# robocon_task1.net
KiCad netlist of a schematic drawn in EAGLE
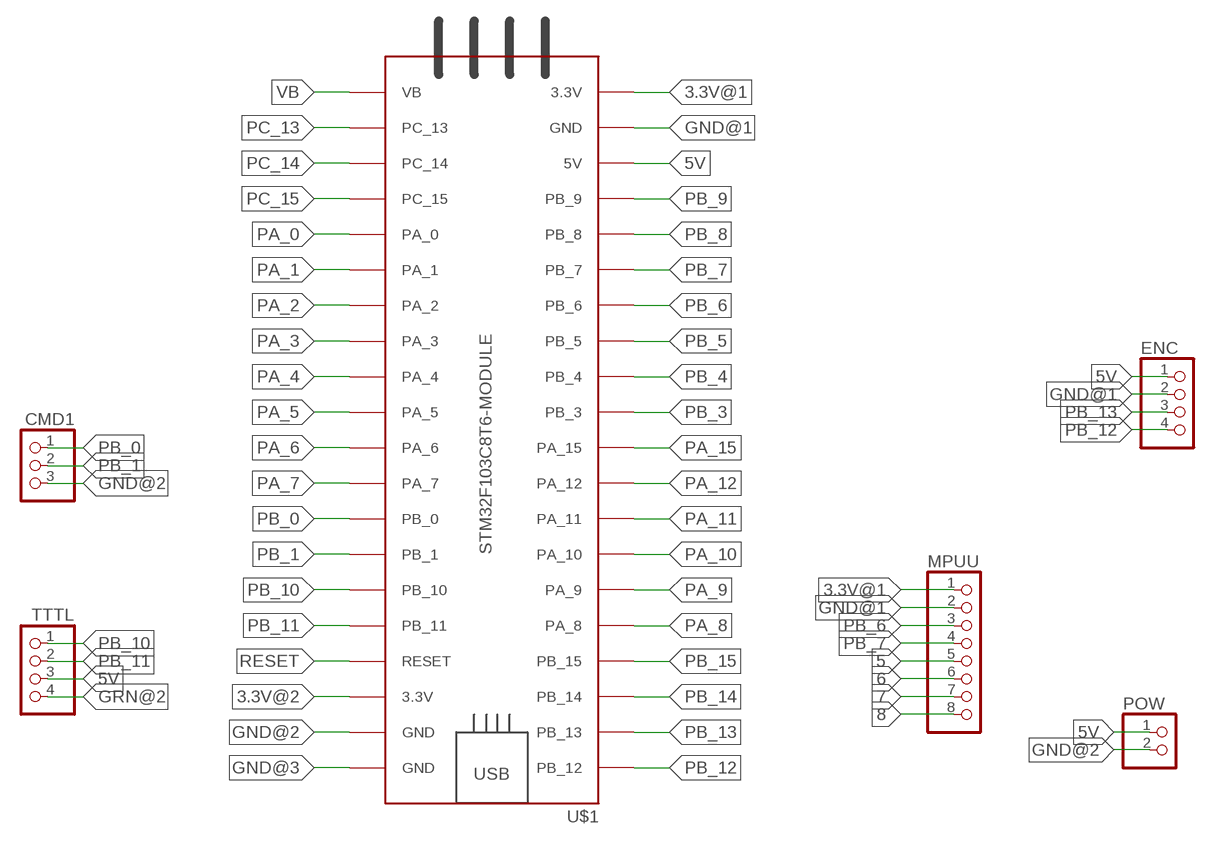
[diagram p0: schematic, sheet 1]

(export (version "E")
  (design (tool "Eeschema 10.0.6"))
  (components
    (comp (ref "CMD1")
      (value "PINHD-1X3")
      (footprint "eagle-import:1X03")
      (libsource (lib "eagle-import") (part "PINHD-1X3"))
    )
    (comp (ref "ENC")
      (value "PINHD-1X4")
      (footprint "eagle-import:1X04")
      (libsource (lib "eagle-import") (part "PINHD-1X4"))
    )
    (comp (ref "MPUU")
      (value "PINHD-1X8")
      (footprint "eagle-import:1X08")
      (libsource (lib "eagle-import") (part "PINHD-1X8"))
    )
    (comp (ref "POW")
      (value "PINHD-2_DATA")
      (footprint "eagle-import:1X02_DATA")
      (libsource (lib "eagle-import") (part "PINHD-2_DATA"))
    )
    (comp (ref "TTTL")
      (value "PINHD-4_DATA")
      (footprint "eagle-import:1X04_DATA")
      (libsource (lib "eagle-import") (part "PINHD-4_DATA"))
    )
    (comp (ref "U$1")
      (value "STM32F103C8T6-MODULE")
      (footprint "eagle-import:STM32F103C8T6-MODULE")
      (libsource (lib "eagle-import") (part "STM32F103C8T6-MODULE"))
    )
  )
  (nets
    (net (code "1") (name "3.3V@1") (class "Default")
      (node (ref "MPUU") (pin "1") (pinfunction "1_1") (pintype "passive"))
      (node (ref "U$1") (pin "3.3V_1") (pinfunction "3.3V_3.3V_1") (pintype "bidirectional"))
    )
    (net (code "2") (name "3.3V@2") (class "Default")
      (node (ref "U$1") (pin "3.3V_2") (pinfunction "3.3V_3.3V_2") (pintype "bidirectional"))
    )
    (net (code "3") (name "5") (class "Default")
      (node (ref "MPUU") (pin "5") (pinfunction "5_5") (pintype "passive"))
    )
    (net (code "4") (name "5V") (class "Default")
      (node (ref "ENC") (pin "1") (pinfunction "1_1") (pintype "passive"))
      (node (ref "POW") (pin "1") (pinfunction "1_1") (pintype "passive"))
      (node (ref "TTTL") (pin "3") (pinfunction "3_3") (pintype "passive"))
      (node (ref "U$1") (pin "5V") (pinfunction "5V_5V") (pintype "bidirectional"))
    )
    (net (code "5") (name "6") (class "Default")
      (node (ref "MPUU") (pin "6") (pinfunction "6_6") (pintype "passive"))
    )
    (net (code "6") (name "7") (class "Default")
      (node (ref "MPUU") (pin "7") (pinfunction "7_7") (pintype "passive"))
    )
    (net (code "7") (name "8") (class "Default")
      (node (ref "MPUU") (pin "8") (pinfunction "8_8") (pintype "passive"))
    )
    (net (code "8") (name "GND@1") (class "Default")
      (node (ref "ENC") (pin "2") (pinfunction "2_2") (pintype "passive"))
      (node (ref "MPUU") (pin "2") (pinfunction "2_2") (pintype "passive"))
      (node (ref "U$1") (pin "GND_1") (pinfunction "GND_GND_1") (pintype "bidirectional"))
    )
    (net (code "9") (name "GND@2") (class "Default")
      (node (ref "CMD1") (pin "3") (pinfunction "3_3") (pintype "passive"))
      (node (ref "POW") (pin "2") (pinfunction "2_2") (pintype "passive"))
      (node (ref "U$1") (pin "GND_2") (pinfunction "GND_GND_2") (pintype "bidirectional"))
    )
    (net (code "10") (name "GND@3") (class "Default")
      (node (ref "U$1") (pin "GND_3") (pinfunction "GND_GND_3") (pintype "power_in"))
    )
    (net (code "11") (name "GRN@2") (class "Default")
      (node (ref "TTTL") (pin "4") (pinfunction "4_4") (pintype "passive"))
    )
    (net (code "12") (name "PA_0") (class "Default")
      (node (ref "U$1") (pin "PA_0") (pinfunction "PA_0_PA_0") (pintype "bidirectional"))
    )
    (net (code "13") (name "PA_1") (class "Default")
      (node (ref "U$1") (pin "PA_1") (pinfunction "PA_1_PA_1") (pintype "bidirectional"))
    )
    (net (code "14") (name "PA_2") (class "Default")
      (node (ref "U$1") (pin "PA_2") (pinfunction "PA_2_PA_2") (pintype "bidirectional"))
    )
    (net (code "15") (name "PA_3") (class "Default")
      (node (ref "U$1") (pin "PA_3") (pinfunction "PA_3_PA_3") (pintype "bidirectional"))
    )
    (net (code "16") (name "PA_4") (class "Default")
      (node (ref "U$1") (pin "PA_4") (pinfunction "PA_4_PA_4") (pintype "bidirectional"))
    )
    (net (code "17") (name "PA_5") (class "Default")
      (node (ref "U$1") (pin "PA_5") (pinfunction "PA_5_PA_5") (pintype "bidirectional"))
    )
    (net (code "18") (name "PA_6") (class "Default")
      (node (ref "U$1") (pin "PA_6") (pinfunction "PA_6_PA_6") (pintype "bidirectional"))
    )
    (net (code "19") (name "PA_7") (class "Default")
      (node (ref "U$1") (pin "PA_7") (pinfunction "PA_7_PA_7") (pintype "bidirectional"))
    )
    (net (code "20") (name "PA_8") (class "Default")
      (node (ref "U$1") (pin "PA_8") (pinfunction "PA_8_PA_8") (pintype "bidirectional"))
    )
    (net (code "21") (name "PA_9") (class "Default")
      (node (ref "U$1") (pin "PA_9") (pinfunction "PA_9_PA_9") (pintype "bidirectional"))
    )
    (net (code "22") (name "PA_10") (class "Default")
      (node (ref "U$1") (pin "PA_10") (pinfunction "PA_10_PA_10") (pintype "bidirectional"))
    )
    (net (code "23") (name "PA_11") (class "Default")
      (node (ref "U$1") (pin "PA_11") (pinfunction "PA_11_PA_11") (pintype "bidirectional"))
    )
    (net (code "24") (name "PA_12") (class "Default")
      (node (ref "U$1") (pin "PA_12") (pinfunction "PA_12_PA_12") (pintype "bidirectional"))
    )
    (net (code "25") (name "PA_15") (class "Default")
      (node (ref "U$1") (pin "PA_15") (pinfunction "PA_15_PA_15") (pintype "bidirectional"))
    )
    (net (code "26") (name "PB_0") (class "Default")
      (node (ref "CMD1") (pin "1") (pinfunction "1_1") (pintype "passive"))
      (node (ref "U$1") (pin "PB_0") (pinfunction "PB_0_PB_0") (pintype "bidirectional"))
    )
    (net (code "27") (name "PB_1") (class "Default")
      (node (ref "CMD1") (pin "2") (pinfunction "2_2") (pintype "passive"))
      (node (ref "U$1") (pin "PB_1") (pinfunction "PB_1_PB_1") (pintype "bidirectional"))
    )
    (net (code "28") (name "PB_3") (class "Default")
      (node (ref "U$1") (pin "PB_3") (pinfunction "PB_3_PB_3") (pintype "bidirectional"))
    )
    (net (code "29") (name "PB_4") (class "Default")
      (node (ref "U$1") (pin "PB_4") (pinfunction "PB_4_PB_4") (pintype "bidirectional"))
    )
    (net (code "30") (name "PB_5") (class "Default")
      (node (ref "U$1") (pin "PB_5") (pinfunction "PB_5_PB_5") (pintype "bidirectional"))
    )
    (net (code "31") (name "PB_6") (class "Default")
      (node (ref "MPUU") (pin "3") (pinfunction "3_3") (pintype "passive"))
      (node (ref "U$1") (pin "PB_6") (pinfunction "PB_6_PB_6") (pintype "bidirectional"))
    )
    (net (code "32") (name "PB_7") (class "Default")
      (node (ref "MPUU") (pin "4") (pinfunction "4_4") (pintype "passive"))
      (node (ref "U$1") (pin "PB_7") (pinfunction "PB_7_PB_7") (pintype "bidirectional"))
    )
    (net (code "33") (name "PB_8") (class "Default")
      (node (ref "U$1") (pin "PB_8") (pinfunction "PB_8_PB_8") (pintype "bidirectional"))
    )
    (net (code "34") (name "PB_9") (class "Default")
      (node (ref "U$1") (pin "PB_9") (pinfunction "PB_9_PB_9") (pintype "bidirectional"))
    )
    (net (code "35") (name "PB_10") (class "Default")
      (node (ref "TTTL") (pin "1") (pinfunction "1_1") (pintype "passive"))
      (node (ref "U$1") (pin "PB_10") (pinfunction "PB_10_PB_10") (pintype "bidirectional"))
    )
    (net (code "36") (name "PB_11") (class "Default")
      (node (ref "TTTL") (pin "2") (pinfunction "2_2") (pintype "passive"))
      (node (ref "U$1") (pin "PB_11") (pinfunction "PB_11_PB_11") (pintype "bidirectional"))
    )
    (net (code "37") (name "PB_12") (class "Default")
      (node (ref "ENC") (pin "4") (pinfunction "4_4") (pintype "passive"))
      (node (ref "U$1") (pin "PB_12") (pinfunction "PB_12_PB_12") (pintype "bidirectional"))
    )
    (net (code "38") (name "PB_13") (class "Default")
      (node (ref "ENC") (pin "3") (pinfunction "3_3") (pintype "passive"))
      (node (ref "U$1") (pin "PB_13") (pinfunction "PB_13_PB_13") (pintype "bidirectional"))
    )
    (net (code "39") (name "PB_14") (class "Default")
      (node (ref "U$1") (pin "PB_14") (pinfunction "PB_14_PB_14") (pintype "bidirectional"))
    )
    (net (code "40") (name "PB_15") (class "Default")
      (node (ref "U$1") (pin "PB_15") (pinfunction "PB_15_PB_15") (pintype "bidirectional"))
    )
    (net (code "41") (name "PC_13") (class "Default")
      (node (ref "U$1") (pin "PC_13") (pinfunction "PC_13_PC_13") (pintype "bidirectional"))
    )
    (net (code "42") (name "PC_14") (class "Default")
      (node (ref "U$1") (pin "PC_14") (pinfunction "PC_14_PC_14") (pintype "bidirectional"))
    )
    (net (code "43") (name "PC_15") (class "Default")
      (node (ref "U$1") (pin "PC_15") (pinfunction "PC_15_PC_15") (pintype "bidirectional"))
    )
    (net (code "44") (name "RESET") (class "Default")
      (node (ref "U$1") (pin "RESET") (pinfunction "RESET_RESET") (pintype "bidirectional"))
    )
    (net (code "45") (name "VB") (class "Default")
      (node (ref "U$1") (pin "VB") (pinfunction "VB_VB") (pintype "bidirectional"))
    )
  )
)
